# Piezo_Driver.net
KiCad netlist of a schematic drawn in Altium Designer
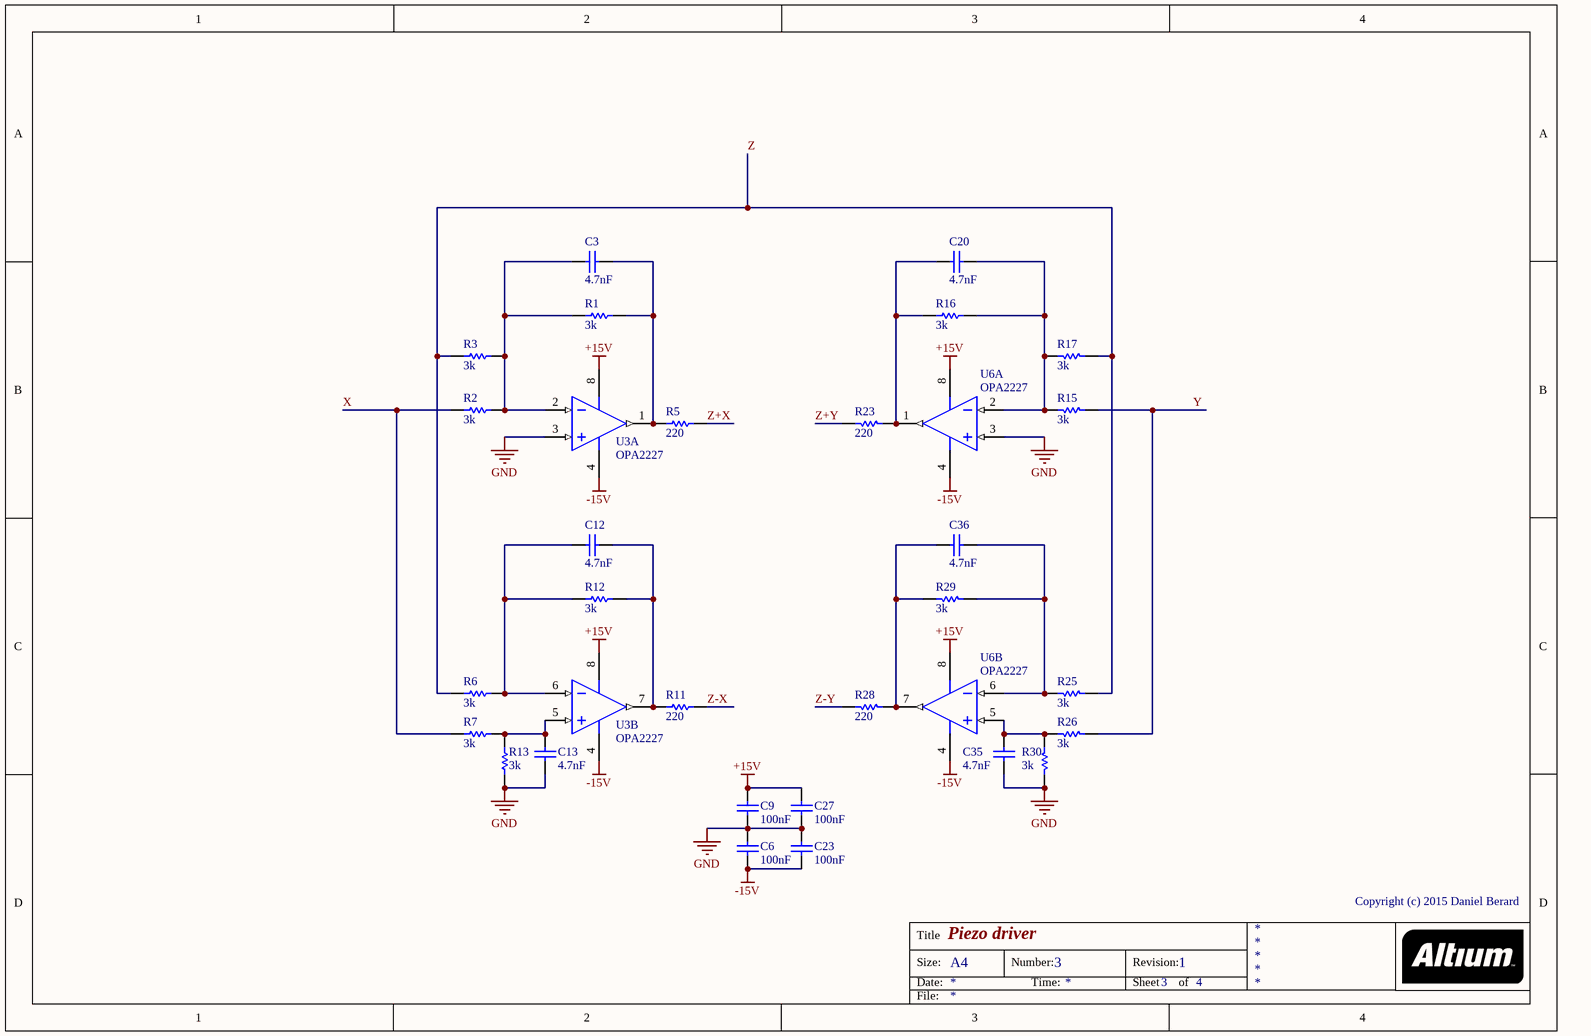
[diagram p0: Piezo Driver.SchDoc]

(export (version "E")
  (design (tool "Eeschema 10.0.6"))
  (components
    (comp (ref "C3")
      (value "4.7nF")
      (footprint "6-0805_N")
      (description "Capacitor")
      (fields (field (name "PUBLISHER") "Altium Limited"))
      (libsource (lib "Miscellaneous Devices") (part "Cap"))
    )
    (comp (ref "C6")
      (value "100nF")
      (footprint "6-0805_N")
      (description "Capacitor")
      (fields (field (name "PUBLISHER") "Altium Limited"))
      (libsource (lib "Miscellaneous Devices") (part "Cap"))
    )
    (comp (ref "C9")
      (value "100nF")
      (footprint "6-0805_N")
      (description "Capacitor")
      (fields (field (name "PUBLISHER") "Altium Limited"))
      (libsource (lib "Miscellaneous Devices") (part "Cap"))
    )
    (comp (ref "C12")
      (value "4.7nF")
      (footprint "6-0805_N")
      (description "Capacitor")
      (fields (field (name "PUBLISHER") "Altium Limited"))
      (libsource (lib "Miscellaneous Devices") (part "Cap"))
    )
    (comp (ref "C13")
      (value "4.7nF")
      (footprint "6-0805_N")
      (description "Capacitor")
      (fields (field (name "PUBLISHER") "Altium Limited"))
      (libsource (lib "Miscellaneous Devices") (part "Cap"))
    )
    (comp (ref "C20")
      (value "4.7nF")
      (footprint "6-0805_N")
      (description "Capacitor")
      (fields (field (name "PUBLISHER") "Altium Limited"))
      (libsource (lib "Miscellaneous Devices") (part "Cap"))
    )
    (comp (ref "C23")
      (value "100nF")
      (footprint "6-0805_N")
      (description "Capacitor")
      (fields (field (name "PUBLISHER") "Altium Limited"))
      (libsource (lib "Miscellaneous Devices") (part "Cap"))
    )
    (comp (ref "C27")
      (value "100nF")
      (footprint "6-0805_N")
      (description "Capacitor")
      (fields (field (name "PUBLISHER") "Altium Limited"))
      (libsource (lib "Miscellaneous Devices") (part "Cap"))
    )
    (comp (ref "C35")
      (value "4.7nF")
      (footprint "6-0805_N")
      (description "Capacitor")
      (fields (field (name "PUBLISHER") "Altium Limited"))
      (libsource (lib "Miscellaneous Devices") (part "Cap"))
    )
    (comp (ref "C36")
      (value "4.7nF")
      (footprint "6-0805_N")
      (description "Capacitor")
      (fields (field (name "PUBLISHER") "Altium Limited"))
      (libsource (lib "Miscellaneous Devices") (part "Cap"))
    )
    (comp (ref "R1")
      (value "3k")
      (footprint "6-0805_N")
      (description "Resistor")
      (fields (field (name "PUBLISHER") "Altium Limited"))
      (libsource (lib "Miscellaneous Devices") (part "Res1"))
    )
    (comp (ref "R2")
      (value "3k")
      (footprint "6-0805_N")
      (description "Resistor")
      (fields (field (name "PUBLISHER") "Altium Limited"))
      (libsource (lib "Miscellaneous Devices") (part "Res1"))
    )
    (comp (ref "R3")
      (value "3k")
      (footprint "6-0805_N")
      (description "Resistor")
      (fields (field (name "PUBLISHER") "Altium Limited"))
      (libsource (lib "Miscellaneous Devices") (part "Res1"))
    )
    (comp (ref "R5")
      (value "220")
      (footprint "6-0805_N")
      (description "Resistor")
      (fields (field (name "PUBLISHER") "Altium Limited"))
      (libsource (lib "Miscellaneous Devices") (part "Res1"))
    )
    (comp (ref "R6")
      (value "3k")
      (footprint "6-0805_N")
      (description "Resistor")
      (fields (field (name "PUBLISHER") "Altium Limited"))
      (libsource (lib "Miscellaneous Devices") (part "Res1"))
    )
    (comp (ref "R7")
      (value "3k")
      (footprint "6-0805_N")
      (description "Resistor")
      (fields (field (name "PUBLISHER") "Altium Limited"))
      (libsource (lib "Miscellaneous Devices") (part "Res1"))
    )
    (comp (ref "R11")
      (value "220")
      (footprint "6-0805_N")
      (description "Resistor")
      (fields (field (name "PUBLISHER") "Altium Limited"))
      (libsource (lib "Miscellaneous Devices") (part "Res1"))
    )
    (comp (ref "R12")
      (value "3k")
      (footprint "6-0805_N")
      (description "Resistor")
      (fields (field (name "PUBLISHER") "Altium Limited"))
      (libsource (lib "Miscellaneous Devices") (part "Res1"))
    )
    (comp (ref "R13")
      (value "3k")
      (footprint "6-0805_N")
      (description "Resistor")
      (fields (field (name "PUBLISHER") "Altium Limited"))
      (libsource (lib "Miscellaneous Devices") (part "Res1"))
    )
    (comp (ref "R15")
      (value "3k")
      (footprint "6-0805_N")
      (description "Resistor")
      (fields (field (name "PUBLISHER") "Altium Limited"))
      (libsource (lib "Miscellaneous Devices") (part "Res1"))
    )
    (comp (ref "R16")
      (value "3k")
      (footprint "6-0805_N")
      (description "Resistor")
      (fields (field (name "PUBLISHER") "Altium Limited"))
      (libsource (lib "Miscellaneous Devices") (part "Res1"))
    )
    (comp (ref "R17")
      (value "3k")
      (footprint "6-0805_N")
      (description "Resistor")
      (fields (field (name "PUBLISHER") "Altium Limited"))
      (libsource (lib "Miscellaneous Devices") (part "Res1"))
    )
    (comp (ref "R23")
      (value "220")
      (footprint "6-0805_N")
      (description "Resistor")
      (fields (field (name "PUBLISHER") "Altium Limited"))
      (libsource (lib "Miscellaneous Devices") (part "Res1"))
    )
    (comp (ref "R25")
      (value "3k")
      (footprint "6-0805_N")
      (description "Resistor")
      (fields (field (name "PUBLISHER") "Altium Limited"))
      (libsource (lib "Miscellaneous Devices") (part "Res1"))
    )
    (comp (ref "R26")
      (value "3k")
      (footprint "6-0805_N")
      (description "Resistor")
      (fields (field (name "PUBLISHER") "Altium Limited"))
      (libsource (lib "Miscellaneous Devices") (part "Res1"))
    )
    (comp (ref "R28")
      (value "220")
      (footprint "6-0805_N")
      (description "Resistor")
      (fields (field (name "PUBLISHER") "Altium Limited"))
      (libsource (lib "Miscellaneous Devices") (part "Res1"))
    )
    (comp (ref "R29")
      (value "3k")
      (footprint "6-0805_N")
      (description "Resistor")
      (fields (field (name "PUBLISHER") "Altium Limited"))
      (libsource (lib "Miscellaneous Devices") (part "Res1"))
    )
    (comp (ref "R30")
      (value "3k")
      (footprint "6-0805_N")
      (description "Resistor")
      (fields (field (name "PUBLISHER") "Altium Limited"))
      (libsource (lib "Miscellaneous Devices") (part "Res1"))
    )
    (comp (ref "U3")
      (value "OPA2227")
      (footprint "ADI-R-8_M")
      (fields
        (field (name "MANUFACTURER") "Analog Devices")
        (field (name "GENERIC PART NUMBER") "AD8676")
        (field (name "PARTNUMBER") "AD8676BRZ")
      )
      (libsource (lib "Altium Content Vault") (part "CMP-0384-01147-2"))
    )
    (comp (ref "U6")
      (value "OPA2227")
      (footprint "ADI-R-8_M")
      (fields
        (field (name "MANUFACTURER") "Analog Devices")
        (field (name "GENERIC PART NUMBER") "AD8676")
        (field (name "PARTNUMBER") "AD8676BRZ")
      )
      (libsource (lib "Altium Content Vault") (part "CMP-0384-01147-2"))
    )
  )
  (nets
    (net (code "1") (name "+15V") (class "Default")
      (node (ref "C27") (pin "2") (pinfunction "2_2") (pintype "passive"))
      (node (ref "C9") (pin "2") (pinfunction "2_2") (pintype "passive"))
      (node (ref "U3") (pin "8") (pinfunction "+V_8") (pintype "power_in"))
      (node (ref "U6") (pin "8") (pinfunction "+V_8") (pintype "power_in"))
    )
    (net (code "2") (name "-15V") (class "Default")
      (node (ref "C23") (pin "1") (pinfunction "1_1") (pintype "passive"))
      (node (ref "C6") (pin "1") (pinfunction "1_1") (pintype "passive"))
      (node (ref "U3") (pin "4") (pinfunction "-V_4") (pintype "power_in"))
      (node (ref "U6") (pin "4") (pinfunction "-V_4") (pintype "power_in"))
    )
    (net (code "3") (name "/X") (class "Default")
      (node (ref "R2") (pin "1") (pinfunction "1_1") (pintype "passive"))
      (node (ref "R7") (pin "1") (pinfunction "1_1") (pintype "passive"))
    )
    (net (code "4") (name "/Y") (class "Default")
      (node (ref "R15") (pin "1") (pinfunction "1_1") (pintype "passive"))
      (node (ref "R26") (pin "1") (pinfunction "1_1") (pintype "passive"))
    )
    (net (code "5") (name "/Z") (class "Default")
      (node (ref "R17") (pin "1") (pinfunction "1_1") (pintype "passive"))
      (node (ref "R25") (pin "1") (pinfunction "1_1") (pintype "passive"))
      (node (ref "R3") (pin "1") (pinfunction "1_1") (pintype "passive"))
      (node (ref "R6") (pin "1") (pinfunction "1_1") (pintype "passive"))
    )
    (net (code "6") (name "/Z+X") (class "Default")
      (node (ref "R5") (pin "2") (pinfunction "2_2") (pintype "passive"))
    )
    (net (code "7") (name "/Z+Y") (class "Default")
      (node (ref "R23") (pin "2") (pinfunction "2_2") (pintype "passive"))
    )
    (net (code "8") (name "/Z-X") (class "Default")
      (node (ref "R11") (pin "2") (pinfunction "2_2") (pintype "passive"))
    )
    (net (code "9") (name "/Z-Y") (class "Default")
      (node (ref "R28") (pin "2") (pinfunction "2_2") (pintype "passive"))
    )
    (net (code "10") (name "GND") (class "Default")
      (node (ref "C13") (pin "1") (pinfunction "1_1") (pintype "passive"))
      (node (ref "C23") (pin "2") (pinfunction "2_2") (pintype "passive"))
      (node (ref "C27") (pin "1") (pinfunction "1_1") (pintype "passive"))
      (node (ref "C35") (pin "1") (pinfunction "1_1") (pintype "passive"))
      (node (ref "C6") (pin "2") (pinfunction "2_2") (pintype "passive"))
      (node (ref "C9") (pin "1") (pinfunction "1_1") (pintype "passive"))
      (node (ref "R13") (pin "1") (pinfunction "1_1") (pintype "passive"))
      (node (ref "R30") (pin "1") (pinfunction "1_1") (pintype "passive"))
      (node (ref "U3") (pin "3") (pinfunction "+IN_A_3") (pintype "input"))
      (node (ref "U6") (pin "3") (pinfunction "+IN_A_3") (pintype "input"))
    )
    (net (code "11") (name "Net-(U3A--IN_A)") (class "Default")
      (node (ref "C3") (pin "1") (pinfunction "1_1") (pintype "passive"))
      (node (ref "R1") (pin "1") (pinfunction "1_1") (pintype "passive"))
      (node (ref "R2") (pin "2") (pinfunction "2_2") (pintype "passive"))
      (node (ref "R3") (pin "2") (pinfunction "2_2") (pintype "passive"))
      (node (ref "U3") (pin "2") (pinfunction "-IN_A_2") (pintype "input"))
    )
    (net (code "12") (name "Net-(U3A-OUT_A)") (class "Default")
      (node (ref "C3") (pin "2") (pinfunction "2_2") (pintype "passive"))
      (node (ref "R1") (pin "2") (pinfunction "2_2") (pintype "passive"))
      (node (ref "R5") (pin "1") (pinfunction "1_1") (pintype "passive"))
      (node (ref "U3") (pin "1") (pinfunction "OUT_A_1") (pintype "output"))
    )
    (net (code "13") (name "Net-(U3B-+IN_B)") (class "Default")
      (node (ref "C13") (pin "2") (pinfunction "2_2") (pintype "passive"))
      (node (ref "R13") (pin "2") (pinfunction "2_2") (pintype "passive"))
      (node (ref "R7") (pin "2") (pinfunction "2_2") (pintype "passive"))
      (node (ref "U3") (pin "5") (pinfunction "+IN_B_5") (pintype "input"))
    )
    (net (code "14") (name "Net-(U3B--IN_B)") (class "Default")
      (node (ref "C12") (pin "1") (pinfunction "1_1") (pintype "passive"))
      (node (ref "R12") (pin "1") (pinfunction "1_1") (pintype "passive"))
      (node (ref "R6") (pin "2") (pinfunction "2_2") (pintype "passive"))
      (node (ref "U3") (pin "6") (pinfunction "-IN_B_6") (pintype "input"))
    )
    (net (code "15") (name "Net-(U3B-OUT_B)") (class "Default")
      (node (ref "C12") (pin "2") (pinfunction "2_2") (pintype "passive"))
      (node (ref "R11") (pin "1") (pinfunction "1_1") (pintype "passive"))
      (node (ref "R12") (pin "2") (pinfunction "2_2") (pintype "passive"))
      (node (ref "U3") (pin "7") (pinfunction "OUT_B_7") (pintype "output"))
    )
    (net (code "16") (name "Net-(U6A--IN_A)") (class "Default")
      (node (ref "C20") (pin "2") (pinfunction "2_2") (pintype "passive"))
      (node (ref "R15") (pin "2") (pinfunction "2_2") (pintype "passive"))
      (node (ref "R16") (pin "2") (pinfunction "2_2") (pintype "passive"))
      (node (ref "R17") (pin "2") (pinfunction "2_2") (pintype "passive"))
      (node (ref "U6") (pin "2") (pinfunction "-IN_A_2") (pintype "input"))
    )
    (net (code "17") (name "Net-(U6A-OUT_A)") (class "Default")
      (node (ref "C20") (pin "1") (pinfunction "1_1") (pintype "passive"))
      (node (ref "R16") (pin "1") (pinfunction "1_1") (pintype "passive"))
      (node (ref "R23") (pin "1") (pinfunction "1_1") (pintype "passive"))
      (node (ref "U6") (pin "1") (pinfunction "OUT_A_1") (pintype "output"))
    )
    (net (code "18") (name "Net-(U6B-+IN_B)") (class "Default")
      (node (ref "C35") (pin "2") (pinfunction "2_2") (pintype "passive"))
      (node (ref "R26") (pin "2") (pinfunction "2_2") (pintype "passive"))
      (node (ref "R30") (pin "2") (pinfunction "2_2") (pintype "passive"))
      (node (ref "U6") (pin "5") (pinfunction "+IN_B_5") (pintype "input"))
    )
    (net (code "19") (name "Net-(U6B--IN_B)") (class "Default")
      (node (ref "C36") (pin "2") (pinfunction "2_2") (pintype "passive"))
      (node (ref "R25") (pin "2") (pinfunction "2_2") (pintype "passive"))
      (node (ref "R29") (pin "1") (pinfunction "1_1") (pintype "passive"))
      (node (ref "U6") (pin "6") (pinfunction "-IN_B_6") (pintype "input"))
    )
    (net (code "20") (name "Net-(U6B-OUT_B)") (class "Default")
      (node (ref "C36") (pin "1") (pinfunction "1_1") (pintype "passive"))
      (node (ref "R28") (pin "1") (pinfunction "1_1") (pintype "passive"))
      (node (ref "R29") (pin "2") (pinfunction "2_2") (pintype "passive"))
      (node (ref "U6") (pin "7") (pinfunction "OUT_B_7") (pintype "output"))
    )
  )
)
